# Smart_Garden.net
KiCad netlist of a schematic drawn in EAGLE
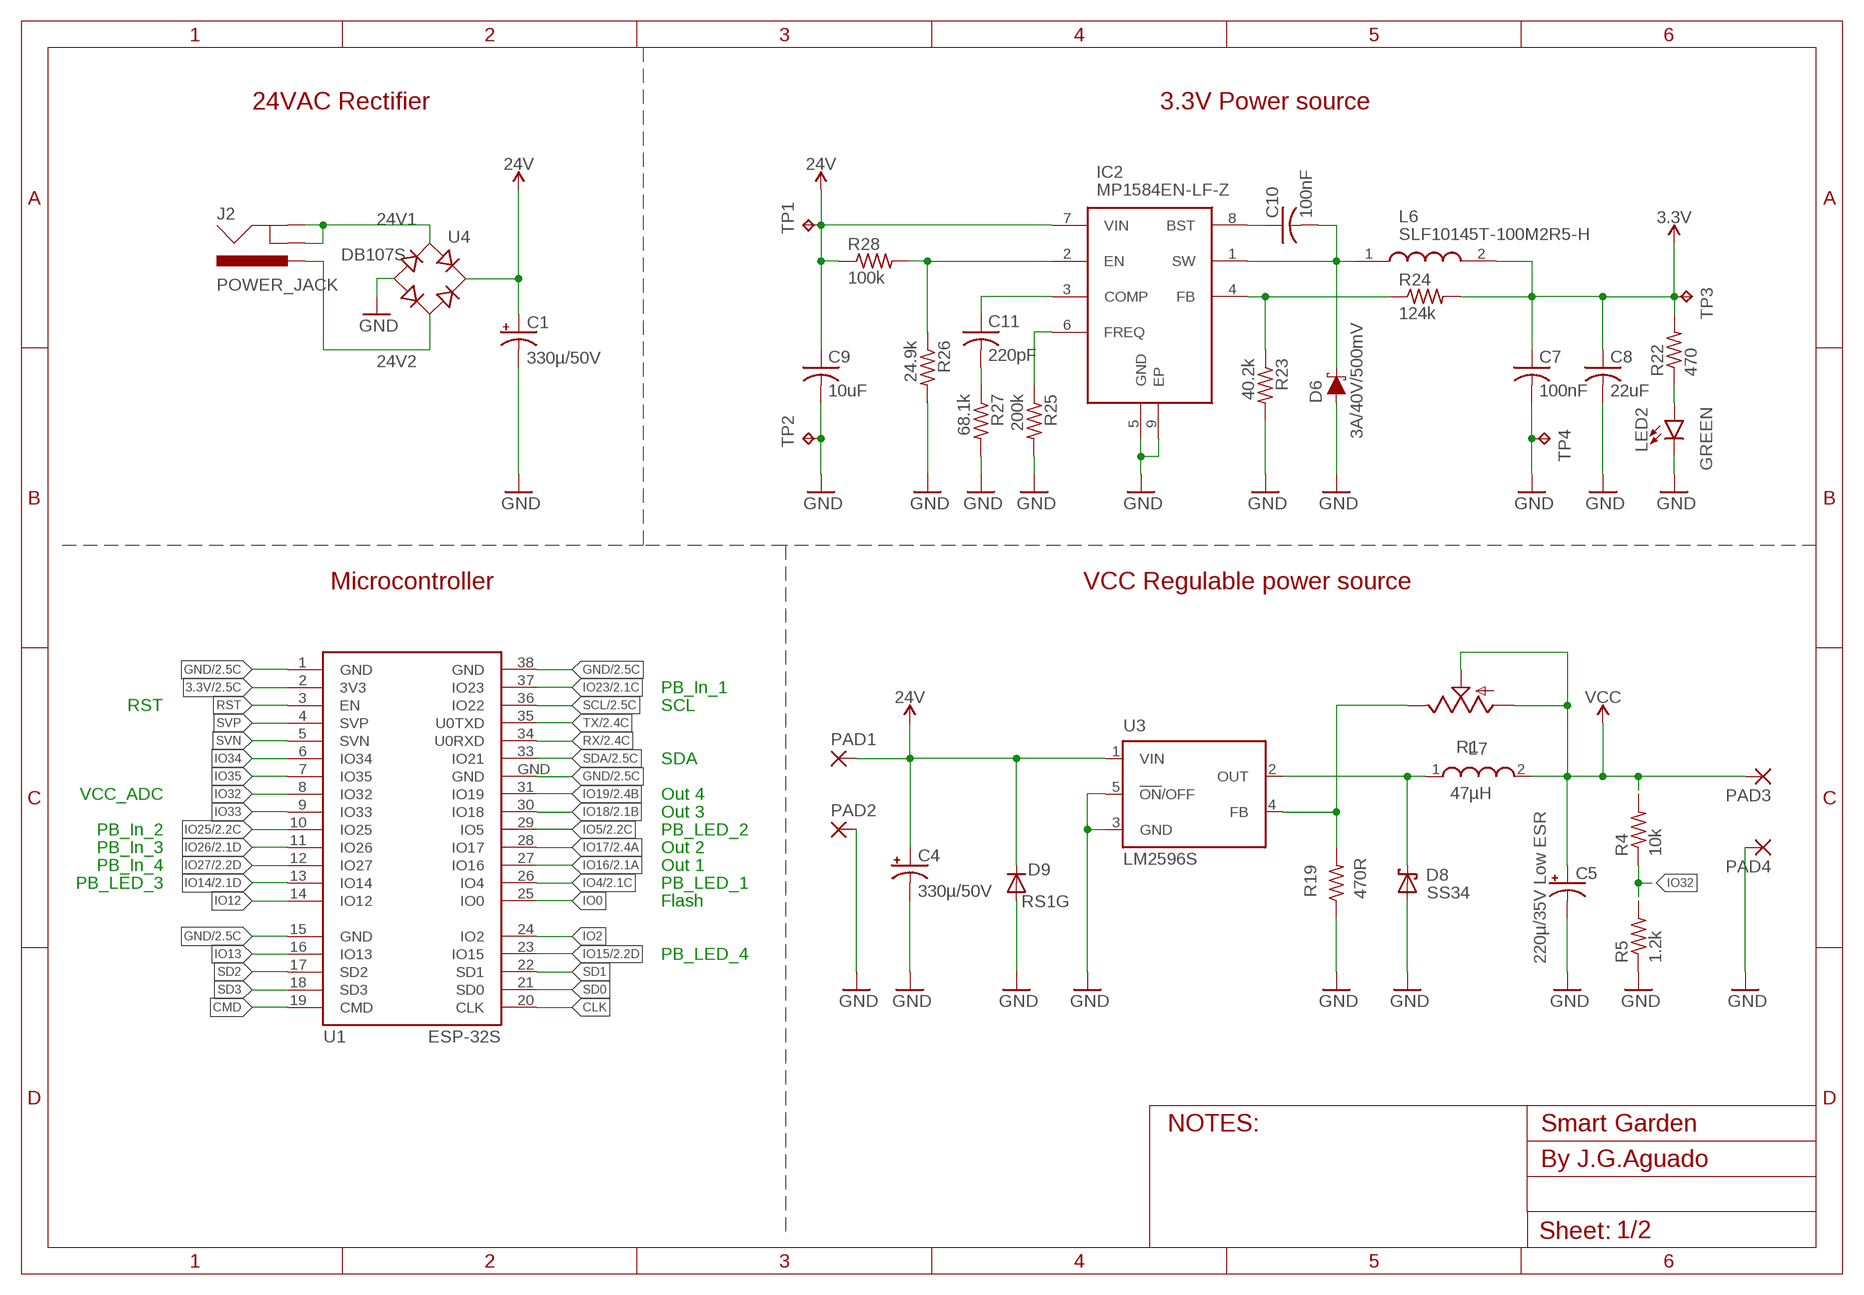
[diagram p0: schematic, sheet 1]
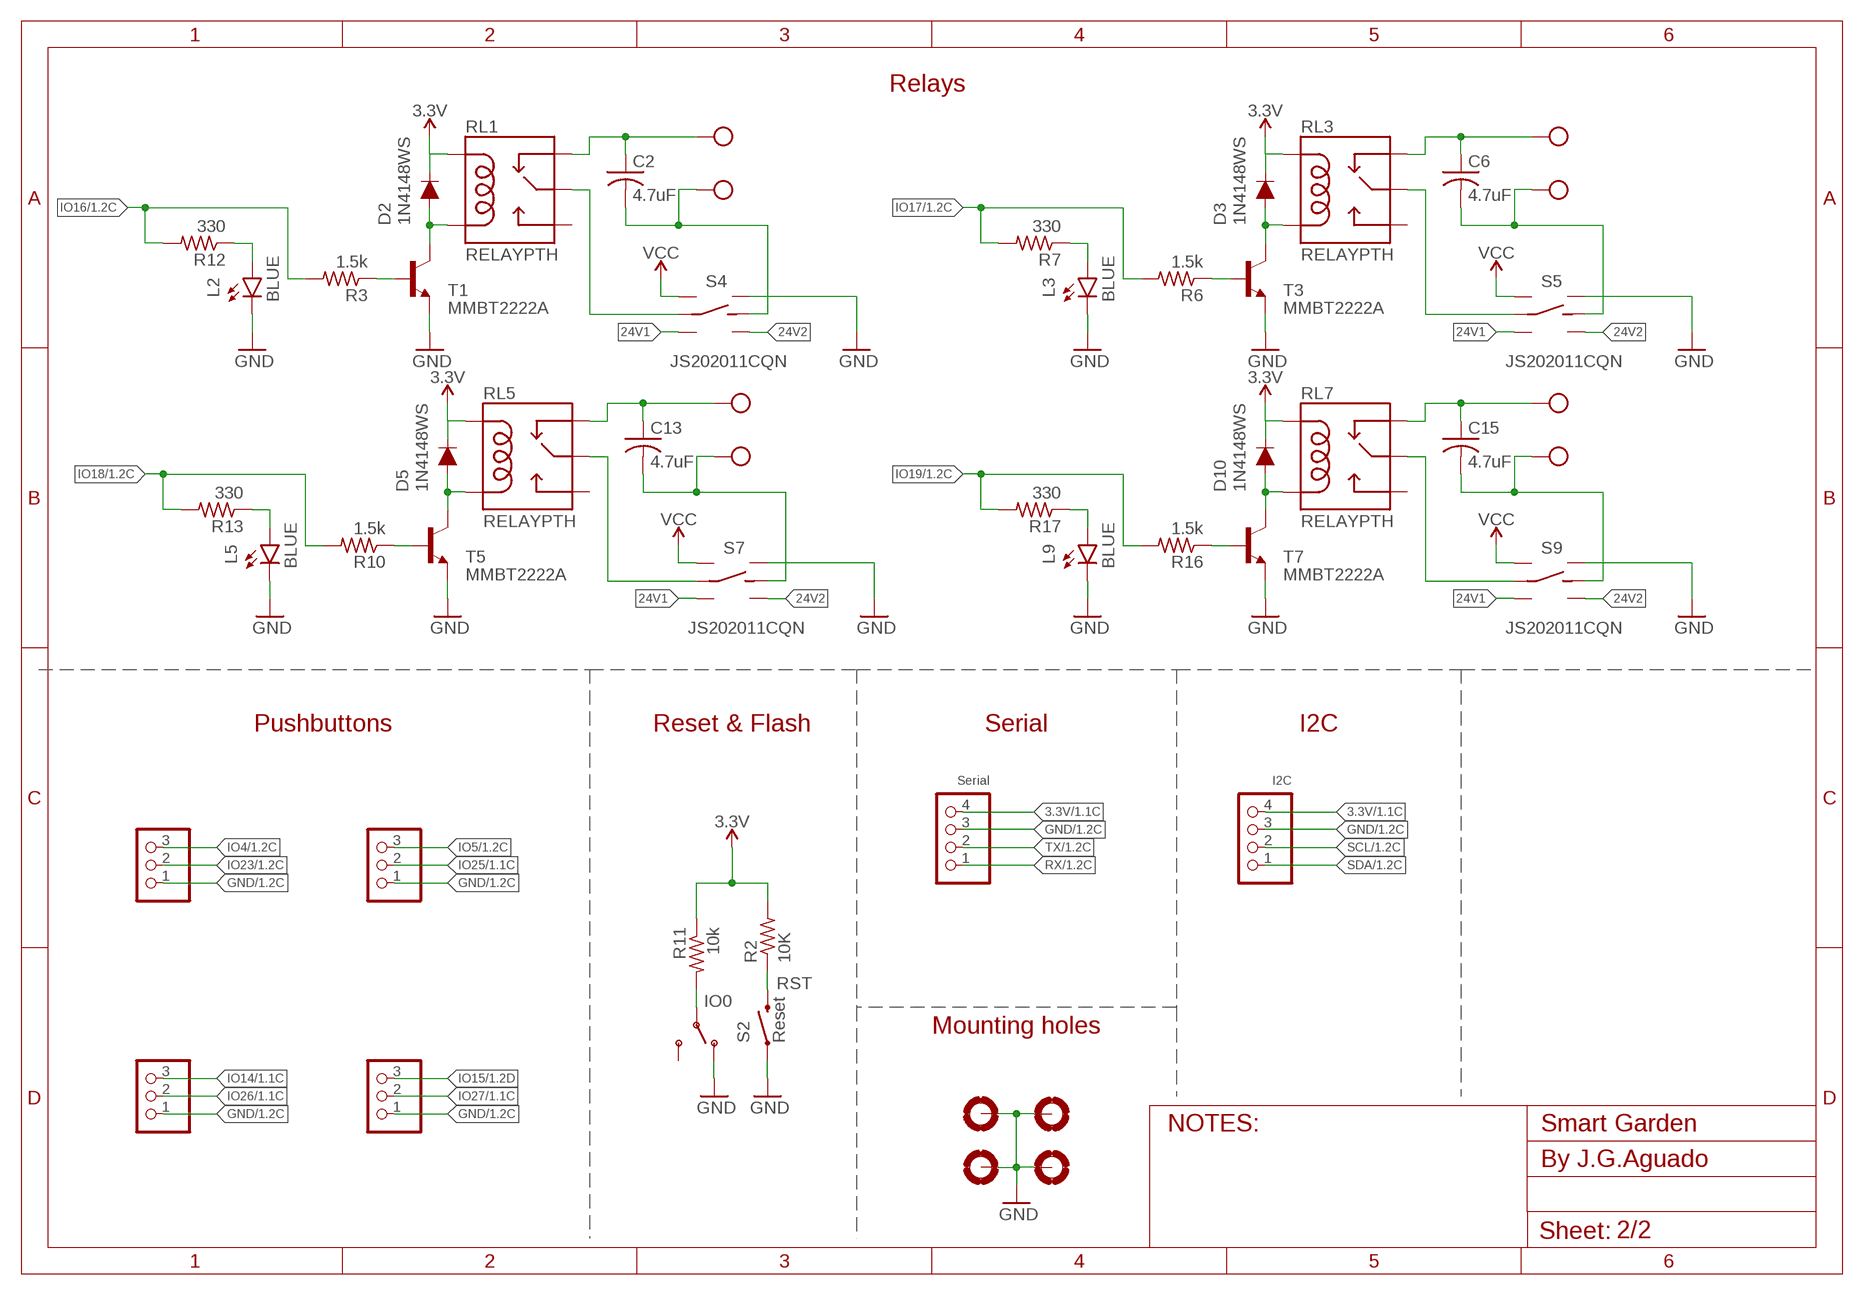
[diagram p1: schematic, sheet 2]

(export (version "E")
  (design (tool "Eeschema 10.0.6"))
  (components
    (comp (ref "C1")
      (value "330µ/50V")
      (footprint "eagle-import:PANASONIC_G")
      (fields (field (name "MF") "Panasonic"))
      (libsource (lib "eagle-import") (part "CPOL-USG"))
    )
    (comp (ref "C4")
      (value "330µ/50V")
      (footprint "eagle-import:PANASONIC_G")
      (fields (field (name "MF") "Panasonic"))
      (libsource (lib "eagle-import") (part "CPOL-USG"))
    )
    (comp (ref "C5")
      (value "220µ/35V Low ESR")
      (footprint "eagle-import:PANASONIC_F")
      (fields (field (name "MF") "Panasonic"))
      (libsource (lib "eagle-import") (part "CPOL-USF"))
    )
    (comp (ref "C7")
      (value "100nF")
      (footprint "eagle-import:C0603")
      (libsource (lib "eagle-import") (part "C-USC0603"))
    )
    (comp (ref "C8")
      (value "22uF")
      (footprint "eagle-import:C0603")
      (libsource (lib "eagle-import") (part "C-USC0603"))
    )
    (comp (ref "C9")
      (value "10uF")
      (footprint "eagle-import:C0603")
      (libsource (lib "eagle-import") (part "C-USC0603"))
    )
    (comp (ref "C10")
      (value "100nF")
      (footprint "eagle-import:C0603")
      (libsource (lib "eagle-import") (part "C-USC0603"))
    )
    (comp (ref "C11")
      (value "220pF")
      (footprint "eagle-import:C0603")
      (libsource (lib "eagle-import") (part "C-USC0603"))
    )
    (comp (ref "D6")
      (value "3A/40V/500mV")
      (footprint "eagle-import:SMA-DIODE")
      (libsource (lib "eagle-import") (part "DIODE-SCHOTTKY-B340A"))
    )
    (comp (ref "D8")
      (value "SS34")
      (footprint "eagle-import:SMB")
      (libsource (lib "eagle-import") (part "SCHOTTKY-DIODESMD"))
    )
    (comp (ref "D9")
      (value "RS1G")
      (footprint "eagle-import:DO214AC")
      (fields (field (name "MF") "multicomp"))
      (libsource (lib "eagle-import") (part "DIODE-DO214AC"))
    )
    (comp (ref "IC2")
      (value "MP1584EN-LF-Z")
      (footprint "eagle-import:SOIC127P600X170-9N")
      (fields (field (name "MOUSER_PART_NUMBER") "946-MP1584ENLFZ"))
      (libsource (lib "eagle-import") (part "MP1584EN-LF-Z"))
    )
    (comp (ref "J2")
      (value "POWER_JACK")
      (footprint "eagle-import:POWER_JACK_PTH")
      (libsource (lib "eagle-import") (part "POWER_JACK"))
    )
    (comp (ref "L6")
      (value "SLF10145T-100M2R5-H")
      (footprint "eagle-import:SLF10145")
      (fields (field (name "MOUSER_PART_NUMBER") "810-SLF10145T100M2R5"))
      (libsource (lib "eagle-import") (part "SLF10145T-100M2R5-H"))
    )
    (comp (ref "L7")
      (value "47µH")
      (footprint "eagle-import:WE-PD_1260_1245_1280_1210")
      (fields (field (name "MF") "Wuerth"))
      (libsource (lib "eagle-import") (part "WE-PD_1260/1245/1280/1210"))
    )
    (comp (ref "LED2")
      (value "GREEN")
      (footprint "eagle-import:LED-0603")
      (libsource (lib "eagle-import") (part "LED-GREEN0603"))
    )
    (comp (ref "PAD1")
      (value "2,54/1,1")
      (footprint "eagle-import:2,54_1,1")
      (libsource (lib "eagle-import") (part "2,54/1,1"))
    )
    (comp (ref "PAD2")
      (value "2,54/1,1")
      (footprint "eagle-import:2,54_1,1")
      (libsource (lib "eagle-import") (part "2,54/1,1"))
    )
    (comp (ref "PAD3")
      (value "2,54/1,1")
      (footprint "eagle-import:2,54_1,1")
      (libsource (lib "eagle-import") (part "2,54/1,1"))
    )
    (comp (ref "PAD4")
      (value "2,54/1,1")
      (footprint "eagle-import:2,54_1,1")
      (libsource (lib "eagle-import") (part "2,54/1,1"))
    )
    (comp (ref "R1")
      (value "TRIM_US-RJ9W")
      (footprint "eagle-import:RJ9W")
      (libsource (lib "eagle-import") (part "TRIM_US-RJ9W"))
    )
    (comp (ref "R4")
      (value "10k")
      (footprint "eagle-import:R0603")
      (libsource (lib "eagle-import") (part "R-US_R0603"))
    )
    (comp (ref "R5")
      (value "1.2k")
      (footprint "eagle-import:R0603")
      (libsource (lib "eagle-import") (part "R-US_R0603"))
    )
    (comp (ref "R19")
      (value "470R")
      (footprint "eagle-import:R1206")
      (libsource (lib "eagle-import") (part "R-US_R1206"))
    )
    (comp (ref "R22")
      (value "470")
      (footprint "eagle-import:R0603")
      (libsource (lib "eagle-import") (part "R-US_R0603"))
    )
    (comp (ref "R23")
      (value "40.2k")
      (footprint "eagle-import:R0603")
      (libsource (lib "eagle-import") (part "R-US_R0603"))
    )
    (comp (ref "R24")
      (value "124k")
      (footprint "eagle-import:R0603")
      (libsource (lib "eagle-import") (part "R-US_R0603"))
    )
    (comp (ref "R25")
      (value "200k")
      (footprint "eagle-import:R0603")
      (libsource (lib "eagle-import") (part "R-US_R0603"))
    )
    (comp (ref "R26")
      (value "24.9k")
      (footprint "eagle-import:R0603")
      (libsource (lib "eagle-import") (part "R-US_R0603"))
    )
    (comp (ref "R27")
      (value "68.1k")
      (footprint "eagle-import:R0603")
      (libsource (lib "eagle-import") (part "R-US_R0603"))
    )
    (comp (ref "R28")
      (value "100k")
      (footprint "eagle-import:R0603")
      (libsource (lib "eagle-import") (part "R-US_R0603"))
    )
    (comp (ref "TP1")
      (value "TPTP20SQ")
      (footprint "eagle-import:TP20SQ")
      (libsource (lib "eagle-import") (part "TPTP20SQ"))
    )
    (comp (ref "TP2")
      (value "TPTP20SQ")
      (footprint "eagle-import:TP20SQ")
      (libsource (lib "eagle-import") (part "TPTP20SQ"))
    )
    (comp (ref "TP3")
      (value "TPTP20SQ")
      (footprint "eagle-import:TP20SQ")
      (libsource (lib "eagle-import") (part "TPTP20SQ"))
    )
    (comp (ref "TP4")
      (value "TPTP20SQ")
      (footprint "eagle-import:TP20SQ")
      (libsource (lib "eagle-import") (part "TPTP20SQ"))
    )
    (comp (ref "U1")
      (value "ESP-32S")
      (footprint "eagle-import:ESP-32S")
      (libsource (lib "eagle-import") (part "ESP-32S"))
    )
    (comp (ref "U3")
      (value "LM2596S")
      (footprint "eagle-import:TO263-5")
      (fields (field (name "MF") "NATIONAL SEMICONDUCTOR") (field (name "MPN") "LM2596S-ADJ/NOPB"))
      (libsource (lib "eagle-import") (part "LM2596S"))
    )
    (comp (ref "U4")
      (value "DB107S")
      (footprint "eagle-import:DBS")
      (libsource (lib "eagle-import") (part "DB?GS107"))
    )
    (comp (ref "C2")
      (value "4.7uF")
      (footprint "eagle-import:C1206")
      (libsource (lib "eagle-import") (part "C-USC1206"))
    )
    (comp (ref "C6")
      (value "4.7uF")
      (footprint "eagle-import:C1206")
      (libsource (lib "eagle-import") (part "C-USC1206"))
    )
    (comp (ref "C13")
      (value "4.7uF")
      (footprint "eagle-import:C1206")
      (libsource (lib "eagle-import") (part "C-USC1206"))
    )
    (comp (ref "C15")
      (value "4.7uF")
      (footprint "eagle-import:C1206")
      (libsource (lib "eagle-import") (part "C-USC1206"))
    )
    (comp (ref "D2")
      (value "1N4148WS")
      (footprint "eagle-import:SOD-323")
      (libsource (lib "eagle-import") (part "DIODE-BAS16J"))
    )
    (comp (ref "D3")
      (value "1N4148WS")
      (footprint "eagle-import:SOD-323")
      (libsource (lib "eagle-import") (part "DIODE-BAS16J"))
    )
    (comp (ref "D5")
      (value "1N4148WS")
      (footprint "eagle-import:SOD-323")
      (libsource (lib "eagle-import") (part "DIODE-BAS16J"))
    )
    (comp (ref "D10")
      (value "1N4148WS")
      (footprint "eagle-import:SOD-323")
      (libsource (lib "eagle-import") (part "DIODE-BAS16J"))
    )
    (comp (ref "H1")
      (value "MOUNT-PAD-ROUND")
      (footprint "eagle-import:3,0-PAD")
      (libsource (lib "eagle-import") (part "MOUNT-PAD-ROUND"))
    )
    (comp (ref "H2")
      (value "MOUNT-PAD-ROUND")
      (footprint "eagle-import:3,0-PAD")
      (libsource (lib "eagle-import") (part "MOUNT-PAD-ROUND"))
    )
    (comp (ref "H3")
      (value "MOUNT-PAD-ROUND")
      (footprint "eagle-import:3,0-PAD")
      (libsource (lib "eagle-import") (part "MOUNT-PAD-ROUND"))
    )
    (comp (ref "H4")
      (value "MOUNT-PAD-ROUND")
      (footprint "eagle-import:3,0-PAD")
      (libsource (lib "eagle-import") (part "MOUNT-PAD-ROUND"))
    )
    (comp (ref "JP1")
      (value "Serial")
      (footprint "eagle-import:1X04")
      (libsource (lib "eagle-import") (part "PINHD-1X4"))
    )
    (comp (ref "JP2")
      (value "PINHD-1X3")
      (footprint "eagle-import:1X03")
      (libsource (lib "eagle-import") (part "PINHD-1X3"))
    )
    (comp (ref "JP3")
      (value "PINHD-1X3")
      (footprint "eagle-import:1X03")
      (libsource (lib "eagle-import") (part "PINHD-1X3"))
    )
    (comp (ref "JP4")
      (value "PINHD-1X3")
      (footprint "eagle-import:1X03")
      (libsource (lib "eagle-import") (part "PINHD-1X3"))
    )
    (comp (ref "JP5")
      (value "PINHD-1X3")
      (footprint "eagle-import:1X03")
      (libsource (lib "eagle-import") (part "PINHD-1X3"))
    )
    (comp (ref "JP6")
      (value "I2C")
      (footprint "eagle-import:1X04")
      (libsource (lib "eagle-import") (part "PINHD-1X4"))
    )
    (comp (ref "L2")
      (value "BLUE")
      (footprint "eagle-import:LED-0603")
      (libsource (lib "eagle-import") (part "LED-BLUE0603"))
    )
    (comp (ref "L3")
      (value "BLUE")
      (footprint "eagle-import:LED-0603")
      (libsource (lib "eagle-import") (part "LED-BLUE0603"))
    )
    (comp (ref "L5")
      (value "BLUE")
      (footprint "eagle-import:LED-0603")
      (libsource (lib "eagle-import") (part "LED-BLUE0603"))
    )
    (comp (ref "L9")
      (value "BLUE")
      (footprint "eagle-import:LED-0603")
      (libsource (lib "eagle-import") (part "LED-BLUE0603"))
    )
    (comp (ref "R2")
      (value "10K")
      (footprint "eagle-import:R0603")
      (libsource (lib "eagle-import") (part "R-US_R0603"))
    )
    (comp (ref "R3")
      (value "1.5k")
      (footprint "eagle-import:R0603")
      (libsource (lib "eagle-import") (part "R-US_R0603"))
    )
    (comp (ref "R6")
      (value "1.5k")
      (footprint "eagle-import:R0603")
      (libsource (lib "eagle-import") (part "R-US_R0603"))
    )
    (comp (ref "R7")
      (value "330")
      (footprint "eagle-import:R0603")
      (libsource (lib "eagle-import") (part "R-US_R0603"))
    )
    (comp (ref "R10")
      (value "1.5k")
      (footprint "eagle-import:R0603")
      (libsource (lib "eagle-import") (part "R-US_R0603"))
    )
    (comp (ref "R11")
      (value "10k")
      (footprint "eagle-import:R0603")
      (libsource (lib "eagle-import") (part "R-US_R0603"))
    )
    (comp (ref "R12")
      (value "330")
      (footprint "eagle-import:R0603")
      (libsource (lib "eagle-import") (part "R-US_R0603"))
    )
    (comp (ref "R13")
      (value "330")
      (footprint "eagle-import:R0603")
      (libsource (lib "eagle-import") (part "R-US_R0603"))
    )
    (comp (ref "R16")
      (value "1.5k")
      (footprint "eagle-import:R0603")
      (libsource (lib "eagle-import") (part "R-US_R0603"))
    )
    (comp (ref "R17")
      (value "330")
      (footprint "eagle-import:R0603")
      (libsource (lib "eagle-import") (part "R-US_R0603"))
    )
    (comp (ref "RL1")
      (value "RELAYPTH")
      (footprint "eagle-import:SRD-05VDC-SL-C")
      (libsource (lib "eagle-import") (part "RELAYPTH"))
    )
    (comp (ref "RL3")
      (value "RELAYPTH")
      (footprint "eagle-import:SRD-05VDC-SL-C")
      (libsource (lib "eagle-import") (part "RELAYPTH"))
    )
    (comp (ref "RL5")
      (value "RELAYPTH")
      (footprint "eagle-import:SRD-05VDC-SL-C")
      (libsource (lib "eagle-import") (part "RELAYPTH"))
    )
    (comp (ref "RL7")
      (value "RELAYPTH")
      (footprint "eagle-import:SRD-05VDC-SL-C")
      (libsource (lib "eagle-import") (part "RELAYPTH"))
    )
    (comp (ref "S1")
      (value "SWITCH_SPDT")
      (footprint "eagle-import:KPS-1290")
      (libsource (lib "eagle-import") (part "SWITCH_SPDT"))
    )
    (comp (ref "S2")
      (value "Reset")
      (footprint "eagle-import:TACTILE_SWITCH_TALL")
      (libsource (lib "eagle-import") (part "SWITCH-MOMENTARY-2SMD-4"))
    )
    (comp (ref "S4")
      (value "JS202011CQN")
      (footprint "eagle-import:DPDT_JS202011CQN")
      (libsource (lib "eagle-import") (part "DPDT_JS202011CQN"))
    )
    (comp (ref "S5")
      (value "JS202011CQN")
      (footprint "eagle-import:DPDT_JS202011CQN")
      (libsource (lib "eagle-import") (part "DPDT_JS202011CQN"))
    )
    (comp (ref "S7")
      (value "JS202011CQN")
      (footprint "eagle-import:DPDT_JS202011CQN")
      (libsource (lib "eagle-import") (part "DPDT_JS202011CQN"))
    )
    (comp (ref "S9")
      (value "JS202011CQN")
      (footprint "eagle-import:DPDT_JS202011CQN")
      (libsource (lib "eagle-import") (part "DPDT_JS202011CQN"))
    )
    (comp (ref "T1")
      (value "MMBT2222A")
      (footprint "eagle-import:SOT23")
      (libsource (lib "eagle-import") (part "BC847"))
    )
    (comp (ref "T3")
      (value "MMBT2222A")
      (footprint "eagle-import:SOT23")
      (libsource (lib "eagle-import") (part "BC847"))
    )
    (comp (ref "T5")
      (value "MMBT2222A")
      (footprint "eagle-import:SOT23")
      (libsource (lib "eagle-import") (part "BC847"))
    )
    (comp (ref "T7")
      (value "MMBT2222A")
      (footprint "eagle-import:SOT23")
      (libsource (lib "eagle-import") (part "BC847"))
    )
    (comp (ref "X2")
      (value "W237-102")
      (footprint "eagle-import:W237-102")
      (fields (field (name "MPN") "237-102"))
      (libsource (lib "eagle-import") (part "W237-102"))
    )
    (comp (ref "X4")
      (value "W237-102")
      (footprint "eagle-import:W237-102")
      (fields (field (name "MPN") "237-102"))
      (libsource (lib "eagle-import") (part "W237-102"))
    )
    (comp (ref "X6")
      (value "W237-102")
      (footprint "eagle-import:W237-102")
      (fields (field (name "MPN") "237-102"))
      (libsource (lib "eagle-import") (part "W237-102"))
    )
    (comp (ref "X7")
      (value "W237-102")
      (footprint "eagle-import:W237-102")
      (fields (field (name "MPN") "237-102"))
      (libsource (lib "eagle-import") (part "W237-102"))
    )
  )
  (nets
    (net (code "1") (name "3.3V") (class "Default")
      (node (ref "C7") (pin "1") (pinfunction "1_1") (pintype "passive"))
      (node (ref "C8") (pin "1") (pinfunction "1_1") (pintype "passive"))
      (node (ref "D10") (pin "C") (pinfunction "C_C") (pintype "passive"))
      (node (ref "D2") (pin "C") (pinfunction "C_C") (pintype "passive"))
      (node (ref "D3") (pin "C") (pinfunction "C_C") (pintype "passive"))
      (node (ref "D5") (pin "C") (pinfunction "C_C") (pintype "passive"))
      (node (ref "JP1") (pin "4") (pinfunction "4_4") (pintype "passive"))
      (node (ref "JP6") (pin "4") (pinfunction "4_4") (pintype "passive"))
      (node (ref "L6") (pin "2") (pinfunction "2_2") (pintype "bidirectional"))
      (node (ref "R11") (pin "1") (pinfunction "1_1") (pintype "passive"))
      (node (ref "R2") (pin "2") (pinfunction "2_2") (pintype "passive"))
      (node (ref "R22") (pin "2") (pinfunction "2_2") (pintype "passive"))
      (node (ref "R24") (pin "2") (pinfunction "2_2") (pintype "passive"))
      (node (ref "RL1") (pin "COIL1") (pinfunction "COIL1_COIL1") (pintype "bidirectional"))
      (node (ref "RL3") (pin "COIL1") (pinfunction "COIL1_COIL1") (pintype "bidirectional"))
      (node (ref "RL5") (pin "COIL1") (pinfunction "COIL1_COIL1") (pintype "bidirectional"))
      (node (ref "RL7") (pin "COIL1") (pinfunction "COIL1_COIL1") (pintype "bidirectional"))
      (node (ref "TP3") (pin "TP") (pinfunction "TP_TP") (pintype "input"))
      (node (ref "U1") (pin "2") (pinfunction "3V3_2") (pintype "power_in"))
    )
    (net (code "2") (name "24V") (class "Default")
      (node (ref "C1") (pin "+") (pinfunction "+_+") (pintype "passive"))
      (node (ref "C4") (pin "+") (pinfunction "+_+") (pintype "passive"))
      (node (ref "C9") (pin "1") (pinfunction "1_1") (pintype "passive"))
      (node (ref "D9") (pin "C") (pinfunction "C_C") (pintype "passive"))
      (node (ref "IC2") (pin "7") (pinfunction "VIN_7") (pintype "power_in"))
      (node (ref "PAD1") (pin "1") (pinfunction "P_1") (pintype "passive"))
      (node (ref "R28") (pin "1") (pinfunction "1_1") (pintype "passive"))
      (node (ref "TP1") (pin "TP") (pinfunction "TP_TP") (pintype "input"))
      (node (ref "U3") (pin "1") (pinfunction "VIN_1") (pintype "input"))
      (node (ref "U4") (pin "+") (pinfunction "+_+") (pintype "passive"))
    )
    (net (code "3") (name "24V1") (class "Default")
      (node (ref "J2") (pin "GND") (pinfunction "GND_GND") (pintype "bidirectional"))
      (node (ref "J2") (pin "GNDBREAK") (pinfunction "GNDBREAK_GNDBREAK") (pintype "bidirectional"))
      (node (ref "S4") (pin "3") (pinfunction "L2_3") (pintype "passive"))
      (node (ref "S5") (pin "3") (pinfunction "L2_3") (pintype "passive"))
      (node (ref "S7") (pin "3") (pinfunction "L2_3") (pintype "passive"))
      (node (ref "S9") (pin "3") (pinfunction "L2_3") (pintype "passive"))
      (node (ref "U4") (pin "AC1") (pinfunction "AC1_AC1") (pintype "passive"))
    )
    (net (code "4") (name "24V2") (class "Default")
      (node (ref "J2") (pin "PWR") (pinfunction "PWR_PWR") (pintype "bidirectional"))
      (node (ref "S4") (pin "6") (pinfunction "R2_6") (pintype "passive"))
      (node (ref "S5") (pin "6") (pinfunction "R2_6") (pintype "passive"))
      (node (ref "S7") (pin "6") (pinfunction "R2_6") (pintype "passive"))
      (node (ref "S9") (pin "6") (pinfunction "R2_6") (pintype "passive"))
      (node (ref "U4") (pin "AC2") (pinfunction "AC2_AC2") (pintype "passive"))
    )
    (net (code "5") (name "CLK") (class "Default")
      (node (ref "U1") (pin "20") (pinfunction "CLK_20") (pintype "bidirectional"))
    )
    (net (code "6") (name "CMD") (class "Default")
      (node (ref "U1") (pin "19") (pinfunction "CMD_19") (pintype "bidirectional"))
    )
    (net (code "7") (name "GND") (class "Default")
      (node (ref "C1") (pin "-") (pinfunction "-_-") (pintype "passive"))
      (node (ref "C4") (pin "-") (pinfunction "-_-") (pintype "passive"))
      (node (ref "C5") (pin "-") (pinfunction "-_-") (pintype "passive"))
      (node (ref "C7") (pin "2") (pinfunction "2_2") (pintype "passive"))
      (node (ref "C8") (pin "2") (pinfunction "2_2") (pintype "passive"))
      (node (ref "C9") (pin "2") (pinfunction "2_2") (pintype "passive"))
      (node (ref "D6") (pin "A") (pinfunction "A_A") (pintype "passive"))
      (node (ref "D8") (pin "A") (pinfunction "A_A") (pintype "passive"))
      (node (ref "D9") (pin "A") (pinfunction "A_A") (pintype "passive"))
      (node (ref "H1") (pin "B3,0") (pinfunction "MOUNT_B3,0") (pintype "passive"))
      (node (ref "H1") (pin "P$2") (pinfunction "MOUNT_P$2") (pintype "passive"))
      (node (ref "H1") (pin "P$3") (pinfunction "MOUNT_P$3") (pintype "passive"))
      (node (ref "H1") (pin "P$4") (pinfunction "MOUNT_P$4") (pintype "passive"))
      (node (ref "H1") (pin "P$5") (pinfunction "MOUNT_P$5") (pintype "passive"))
      (node (ref "H1") (pin "P$6") (pinfunction "MOUNT_P$6") (pintype "passive"))
      (node (ref "H1") (pin "P$7") (pinfunction "MOUNT_P$7") (pintype "passive"))
      (node (ref "H1") (pin "P$8") (pinfunction "MOUNT_P$8") (pintype "passive"))
      (node (ref "H1") (pin "P$9") (pinfunction "MOUNT_P$9") (pintype "passive"))
      (node (ref "H2") (pin "B3,0") (pinfunction "MOUNT_B3,0") (pintype "passive"))
      (node (ref "H2") (pin "P$2") (pinfunction "MOUNT_P$2") (pintype "passive"))
      (node (ref "H2") (pin "P$3") (pinfunction "MOUNT_P$3") (pintype "passive"))
      (node (ref "H2") (pin "P$4") (pinfunction "MOUNT_P$4") (pintype "passive"))
      (node (ref "H2") (pin "P$5") (pinfunction "MOUNT_P$5") (pintype "passive"))
      (node (ref "H2") (pin "P$6") (pinfunction "MOUNT_P$6") (pintype "passive"))
      (node (ref "H2") (pin "P$7") (pinfunction "MOUNT_P$7") (pintype "passive"))
      (node (ref "H2") (pin "P$8") (pinfunction "MOUNT_P$8") (pintype "passive"))
      (node (ref "H2") (pin "P$9") (pinfunction "MOUNT_P$9") (pintype "passive"))
      (node (ref "H3") (pin "B3,0") (pinfunction "MOUNT_B3,0") (pintype "passive"))
      (node (ref "H3") (pin "P$2") (pinfunction "MOUNT_P$2") (pintype "passive"))
      (node (ref "H3") (pin "P$3") (pinfunction "MOUNT_P$3") (pintype "passive"))
      (node (ref "H3") (pin "P$4") (pinfunction "MOUNT_P$4") (pintype "passive"))
      (node (ref "H3") (pin "P$5") (pinfunction "MOUNT_P$5") (pintype "passive"))
      (node (ref "H3") (pin "P$6") (pinfunction "MOUNT_P$6") (pintype "passive"))
      (node (ref "H3") (pin "P$7") (pinfunction "MOUNT_P$7") (pintype "passive"))
      (node (ref "H3") (pin "P$8") (pinfunction "MOUNT_P$8") (pintype "passive"))
      (node (ref "H3") (pin "P$9") (pinfunction "MOUNT_P$9") (pintype "passive"))
      (node (ref "H4") (pin "B3,0") (pinfunction "MOUNT_B3,0") (pintype "passive"))
      (node (ref "H4") (pin "P$2") (pinfunction "MOUNT_P$2") (pintype "passive"))
      (node (ref "H4") (pin "P$3") (pinfunction "MOUNT_P$3") (pintype "passive"))
      (node (ref "H4") (pin "P$4") (pinfunction "MOUNT_P$4") (pintype "passive"))
      (node (ref "H4") (pin "P$5") (pinfunction "MOUNT_P$5") (pintype "passive"))
      (node (ref "H4") (pin "P$6") (pinfunction "MOUNT_P$6") (pintype "passive"))
      (node (ref "H4") (pin "P$7") (pinfunction "MOUNT_P$7") (pintype "passive"))
      (node (ref "H4") (pin "P$8") (pinfunction "MOUNT_P$8") (pintype "passive"))
      (node (ref "H4") (pin "P$9") (pinfunction "MOUNT_P$9") (pintype "passive"))
      (node (ref "IC2") (pin "5") (pinfunction "GND_5") (pintype "power_in"))
      (node (ref "IC2") (pin "9") (pinfunction "EP_9") (pintype "bidirectional"))
      (node (ref "JP1") (pin "3") (pinfunction "3_3") (pintype "passive"))
      (node (ref "JP2") (pin "1") (pinfunction "1_1") (pintype "passive"))
      (node (ref "JP3") (pin "1") (pinfunction "1_1") (pintype "passive"))
      (node (ref "JP4") (pin "1") (pinfunction "1_1") (pintype "passive"))
      (node (ref "JP5") (pin "1") (pinfunction "1_1") (pintype "passive"))
      (node (ref "JP6") (pin "3") (pinfunction "3_3") (pintype "passive"))
      (node (ref "L2") (pin "C") (pinfunction "C_C") (pintype "passive"))
      (node (ref "L3") (pin "C") (pinfunction "C_C") (pintype "passive"))
      (node (ref "L5") (pin "C") (pinfunction "C_C") (pintype "passive"))
      (node (ref "L9") (pin "C") (pinfunction "C_C") (pintype "passive"))
      (node (ref "LED2") (pin "C") (pinfunction "C_C") (pintype "passive"))
      (node (ref "PAD2") (pin "1") (pinfunction "P_1") (pintype "passive"))
      (node (ref "PAD4") (pin "1") (pinfunction "P_1") (pintype "passive"))
      (node (ref "R19") (pin "1") (pinfunction "1_1") (pintype "passive"))
      (node (ref "R23") (pin "2") (pinfunction "2_2") (pintype "passive"))
      (node (ref "R25") (pin "2") (pinfunction "2_2") (pintype "passive"))
      (node (ref "R26") (pin "2") (pinfunction "2_2") (pintype "passive"))
      (node (ref "R27") (pin "2") (pinfunction "2_2") (pintype "passive"))
      (node (ref "R5") (pin "1") (pinfunction "1_1") (pintype "passive"))
      (node (ref "S1") (pin "O") (pinfunction "O_O") (pintype "passive"))
      (node (ref "S2") (pin "A2") (pinfunction "1_A2") (pintype "passive"))
      (node (ref "S4") (pin "4") (pinfunction "R1_4") (pintype "passive"))
      (node (ref "S5") (pin "4") (pinfunction "R1_4") (pintype "passive"))
      (node (ref "S7") (pin "4") (pinfunction "R1_4") (pintype "passive"))
      (node (ref "S9") (pin "4") (pinfunction "R1_4") (pintype "passive"))
      (node (ref "T1") (pin "2") (pinfunction "E_2") (pintype "passive"))
      (node (ref "T3") (pin "2") (pinfunction "E_2") (pintype "passive"))
      (node (ref "T5") (pin "2") (pinfunction "E_2") (pintype "passive"))
      (node (ref "T7") (pin "2") (pinfunction "E_2") (pintype "passive"))
      (node (ref "TP2") (pin "TP") (pinfunction "TP_TP") (pintype "input"))
      (node (ref "TP4") (pin "TP") (pinfunction "TP_TP") (pintype "input"))
      (node (ref "U1") (pin "1") (pinfunction "GND_1") (pintype "power_in"))
      (node (ref "U1") (pin "15") (pinfunction "GND_15") (pintype "power_in"))
      (node (ref "U1") (pin "38") (pinfunction "GND_38") (pintype "power_in"))
      (node (ref "U1") (pin "GND") (pinfunction "GND_GND") (pintype "power_in"))
      (node (ref "U3") (pin "3") (pinfunction "GND_3") (pintype "power_in"))
      (node (ref "U3") (pin "5") (pinfunction "~{ON}/OFF_5") (pintype "input"))
      (node (ref "U4") (pin "-") (pinfunction "-_-") (pintype "passive"))
    )
    (net (code "8") (name "IO0") (class "Default")
      (node (ref "R11") (pin "2") (pinfunction "2_2") (pintype "passive"))
      (node (ref "S1") (pin "P") (pinfunction "P_P") (pintype "passive"))
      (node (ref "U1") (pin "25") (pinfunction "IO0_25") (pintype "bidirectional"))
    )
    (net (code "9") (name "IO2") (class "Default")
      (node (ref "U1") (pin "24") (pinfunction "IO2_24") (pintype "bidirectional"))
    )
    (net (code "10") (name "IO4") (class "Default")
      (node (ref "JP5") (pin "3") (pinfunction "3_3") (pintype "passive"))
      (node (ref "U1") (pin "26") (pinfunction "IO4_26") (pintype "bidirectional"))
    )
    (net (code "11") (name "IO5") (class "Default")
      (node (ref "JP4") (pin "3") (pinfunction "3_3") (pintype "passive"))
      (node (ref "U1") (pin "29") (pinfunction "IO5_29") (pintype "bidirectional"))
    )
    (net (code "12") (name "IO12") (class "Default")
      (node (ref "U1") (pin "14") (pinfunction "IO12_14") (pintype "bidirectional"))
    )
    (net (code "13") (name "IO13") (class "Default")
      (node (ref "U1") (pin "16") (pinfunction "IO13_16") (pintype "bidirectional"))
    )
    (net (code "14") (name "IO14") (class "Default")
      (node (ref "JP3") (pin "3") (pinfunction "3_3") (pintype "passive"))
      (node (ref "U1") (pin "13") (pinfunction "IO14_13") (pintype "bidirectional"))
    )
    (net (code "15") (name "IO15") (class "Default")
      (node (ref "JP2") (pin "3") (pinfunction "3_3") (pintype "passive"))
      (node (ref "U1") (pin "23") (pinfunction "IO15_23") (pintype "bidirectional"))
    )
    (net (code "16") (name "IO16") (class "Default")
      (node (ref "R12") (pin "2") (pinfunction "2_2") (pintype "passive"))
      (node (ref "R3") (pin "2") (pinfunction "2_2") (pintype "passive"))
      (node (ref "U1") (pin "27") (pinfunction "IO16_27") (pintype "bidirectional"))
    )
    (net (code "17") (name "IO17") (class "Default")
      (node (ref "R6") (pin "2") (pinfunction "2_2") (pintype "passive"))
      (node (ref "R7") (pin "2") (pinfunction "2_2") (pintype "passive"))
      (node (ref "U1") (pin "28") (pinfunction "IO17_28") (pintype "bidirectional"))
    )
    (net (code "18") (name "IO18") (class "Default")
      (node (ref "R10") (pin "2") (pinfunction "2_2") (pintype "passive"))
      (node (ref "R13") (pin "2") (pinfunction "2_2") (pintype "passive"))
      (node (ref "U1") (pin "30") (pinfunction "IO18_30") (pintype "bidirectional"))
    )
    (net (code "19") (name "IO19") (class "Default")
      (node (ref "R16") (pin "2") (pinfunction "2_2") (pintype "passive"))
      (node (ref "R17") (pin "2") (pinfunction "2_2") (pintype "passive"))
      (node (ref "U1") (pin "31") (pinfunction "IO19_31") (pintype "bidirectional"))
    )
    (net (code "20") (name "IO23") (class "Default")
      (node (ref "JP5") (pin "2") (pinfunction "2_2") (pintype "passive"))
      (node (ref "U1") (pin "37") (pinfunction "IO23_37") (pintype "bidirectional"))
    )
    (net (code "21") (name "IO25") (class "Default")
      (node (ref "JP4") (pin "2") (pinfunction "2_2") (pintype "passive"))
      (node (ref "U1") (pin "10") (pinfunction "IO25_10") (pintype "bidirectional"))
    )
    (net (code "22") (name "IO26") (class "Default")
      (node (ref "JP3") (pin "2") (pinfunction "2_2") (pintype "passive"))
      (node (ref "U1") (pin "11") (pinfunction "IO26_11") (pintype "bidirectional"))
    )
    (net (code "23") (name "IO27") (class "Default")
      (node (ref "JP2") (pin "2") (pinfunction "2_2") (pintype "passive"))
      (node (ref "U1") (pin "12") (pinfunction "IO27_12") (pintype "bidirectional"))
    )
    (net (code "24") (name "IO32") (class "Default")
      (node (ref "R4") (pin "1") (pinfunction "1_1") (pintype "passive"))
      (node (ref "R5") (pin "2") (pinfunction "2_2") (pintype "passive"))
      (node (ref "U1") (pin "8") (pinfunction "IO32_8") (pintype "bidirectional"))
    )
    (net (code "25") (name "IO33") (class "Default")
      (node (ref "U1") (pin "9") (pinfunction "IO33_9") (pintype "bidirectional"))
    )
    (net (code "26") (name "IO34") (class "Default")
      (node (ref "U1") (pin "6") (pinfunction "IO34_6") (pintype "bidirectional"))
    )
    (net (code "27") (name "IO35") (class "Default")
      (node (ref "U1") (pin "7") (pinfunction "IO35_7") (pintype "bidirectional"))
    )
    (net (code "28") (name "Net-(C11-Pad2)") (class "Default")
      (node (ref "C11") (pin "2") (pinfunction "2_2") (pintype "passive"))
      (node (ref "R27") (pin "1") (pinfunction "1_1") (pintype "passive"))
    )
    (net (code "29") (name "Net-(IC2-BST)") (class "Default")
      (node (ref "C10") (pin "1") (pinfunction "1_1") (pintype "passive"))
      (node (ref "IC2") (pin "8") (pinfunction "BST_8") (pintype "input"))
    )
    (net (code "30") (name "Net-(IC2-COMP)") (class "Default")
      (node (ref "C11") (pin "1") (pinfunction "1_1") (pintype "passive"))
      (node (ref "IC2") (pin "3") (pinfunction "COMP_3") (pintype "bidirectional"))
    )
    (net (code "31") (name "Net-(IC2-EN)") (class "Default")
      (node (ref "IC2") (pin "2") (pinfunction "EN_2") (pintype "input"))
      (node (ref "R26") (pin "1") (pinfunction "1_1") (pintype "passive"))
      (node (ref "R28") (pin "2") (pinfunction "2_2") (pintype "passive"))
    )
    (net (code "32") (name "Net-(IC2-FB)") (class "Default")
      (node (ref "IC2") (pin "4") (pinfunction "FB_4") (pintype "input"))
      (node (ref "R23") (pin "1") (pinfunction "1_1") (pintype "passive"))
      (node (ref "R24") (pin "1") (pinfunction "1_1") (pintype "passive"))
    )
    (net (code "33") (name "Net-(IC2-FREQ)") (class "Default")
      (node (ref "IC2") (pin "6") (pinfunction "FREQ_6") (pintype "input"))
      (node (ref "R25") (pin "1") (pinfunction "1_1") (pintype "passive"))
    )
    (net (code "34") (name "Net-(IC2-SW)") (class "Default")
      (node (ref "C10") (pin "2") (pinfunction "2_2") (pintype "passive"))
      (node (ref "D6") (pin "C") (pinfunction "C_C") (pintype "passive"))
      (node (ref "IC2") (pin "1") (pinfunction "SW_1") (pintype "output"))
      (node (ref "L6") (pin "1") (pinfunction "1_1") (pintype "bidirectional"))
    )
    (net (code "35") (name "Net-(L2-PadA)") (class "Default")
      (node (ref "L2") (pin "A") (pinfunction "A_A") (pintype "passive"))
      (node (ref "R12") (pin "1") (pinfunction "1_1") (pintype "passive"))
    )
    (net (code "36") (name "Net-(L3-PadA)") (class "Default")
      (node (ref "L3") (pin "A") (pinfunction "A_A") (pintype "passive"))
      (node (ref "R7") (pin "1") (pinfunction "1_1") (pintype "passive"))
    )
    (net (code "37") (name "Net-(L5-PadA)") (class "Default")
      (node (ref "L5") (pin "A") (pinfunction "A_A") (pintype "passive"))
      (node (ref "R13") (pin "1") (pinfunction "1_1") (pintype "passive"))
    )
    (net (code "38") (name "Net-(L9-PadA)") (class "Default")
      (node (ref "L9") (pin "A") (pinfunction "A_A") (pintype "passive"))
      (node (ref "R17") (pin "1") (pinfunction "1_1") (pintype "passive"))
    )
    (net (code "39") (name "Net-(LED2-PadA)") (class "Default")
      (node (ref "LED2") (pin "A") (pinfunction "A_A") (pintype "passive"))
      (node (ref "R22") (pin "1") (pinfunction "1_1") (pintype "passive"))
    )
    (net (code "40") (name "Net-(RL1-SWCLOSE)") (class "Default")
      (node (ref "C2") (pin "1") (pinfunction "1_1") (pintype "passive"))
      (node (ref "RL1") (pin "SWCLOSED") (pinfunction "SWCLOSE_SWCLOSED") (pintype "bidirectional"))
      (node (ref "X7") (pin "1") (pinfunction "KL_1") (pintype "passive"))
    )
    (net (code "41") (name "Net-(RL3-SWCLOSE)") (class "Default")
      (node (ref "C6") (pin "1") (pinfunction "1_1") (pintype "passive"))
      (node (ref "RL3") (pin "SWCLOSED") (pinfunction "SWCLOSE_SWCLOSED") (pintype "bidirectional"))
      (node (ref "X2") (pin "1") (pinfunction "KL_1") (pintype "passive"))
    )
    (net (code "42") (name "Net-(RL5-SWCLOSE)") (class "Default")
      (node (ref "C13") (pin "1") (pinfunction "1_1") (pintype "passive"))
      (node (ref "RL5") (pin "SWCLOSED") (pinfunction "SWCLOSE_SWCLOSED") (pintype "bidirectional"))
      (node (ref "X4") (pin "1") (pinfunction "KL_1") (pintype "passive"))
    )
    (net (code "43") (name "Net-(RL7-SWCLOSE)") (class "Default")
      (node (ref "C15") (pin "1") (pinfunction "1_1") (pintype "passive"))
      (node (ref "RL7") (pin "SWCLOSED") (pinfunction "SWCLOSE_SWCLOSED") (pintype "bidirectional"))
      (node (ref "X6") (pin "1") (pinfunction "KL_1") (pintype "passive"))
    )
    (net (code "44") (name "Net-(S4-LC)") (class "Default")
      (node (ref "RL1") (pin "SWCOMMON") (pinfunction "SWCOMMON_SWCOMMON") (pintype "bidirectional"))
      (node (ref "S4") (pin "2") (pinfunction "LC_2") (pintype "passive"))
    )
    (net (code "45") (name "Net-(S4-RC)") (class "Default")
      (node (ref "C2") (pin "2") (pinfunction "2_2") (pintype "passive"))
      (node (ref "S4") (pin "5") (pinfunction "RC_5") (pintype "passive"))
      (node (ref "X7") (pin "2") (pinfunction "KL_2") (pintype "passive"))
    )
    (net (code "46") (name "Net-(S5-LC)") (class "Default")
      (node (ref "RL3") (pin "SWCOMMON") (pinfunction "SWCOMMON_SWCOMMON") (pintype "bidirectional"))
      (node (ref "S5") (pin "2") (pinfunction "LC_2") (pintype "passive"))
    )
    (net (code "47") (name "Net-(S5-RC)") (class "Default")
      (node (ref "C6") (pin "2") (pinfunction "2_2") (pintype "passive"))
      (node (ref "S5") (pin "5") (pinfunction "RC_5") (pintype "passive"))
      (node (ref "X2") (pin "2") (pinfunction "KL_2") (pintype "passive"))
    )
    (net (code "48") (name "Net-(S7-LC)") (class "Default")
      (node (ref "RL5") (pin "SWCOMMON") (pinfunction "SWCOMMON_SWCOMMON") (pintype "bidirectional"))
      (node (ref "S7") (pin "2") (pinfunction "LC_2") (pintype "passive"))
    )
    (net (code "49") (name "Net-(S7-RC)") (class "Default")
      (node (ref "C13") (pin "2") (pinfunction "2_2") (pintype "passive"))
      (node (ref "S7") (pin "5") (pinfunction "RC_5") (pintype "passive"))
      (node (ref "X4") (pin "2") (pinfunction "KL_2") (pintype "passive"))
    )
    (net (code "50") (name "Net-(S9-LC)") (class "Default")
      (node (ref "RL7") (pin "SWCOMMON") (pinfunction "SWCOMMON_SWCOMMON") (pintype "bidirectional"))
      (node (ref "S9") (pin "2") (pinfunction "LC_2") (pintype "passive"))
    )
    (net (code "51") (name "Net-(S9-RC)") (class "Default")
      (node (ref "C15") (pin "2") (pinfunction "2_2") (pintype "passive"))
      (node (ref "S9") (pin "5") (pinfunction "RC_5") (pintype "passive"))
      (node (ref "X6") (pin "2") (pinfunction "KL_2") (pintype "passive"))
    )
    (net (code "52") (name "Net-(T1-B)") (class "Default")
      (node (ref "R3") (pin "1") (pinfunction "1_1") (pintype "passive"))
      (node (ref "T1") (pin "1") (pinfunction "B_1") (pintype "passive"))
    )
    (net (code "53") (name "Net-(T1-C)") (class "Default")
      (node (ref "D2") (pin "A") (pinfunction "A_A") (pintype "passive"))
      (node (ref "RL1") (pin "COIL0") (pinfunction "COIL0_COIL0") (pintype "bidirectional"))
      (node (ref "T1") (pin "3") (pinfunction "C_3") (pintype "passive"))
    )
    (net (code "54") (name "Net-(T3-B)") (class "Default")
      (node (ref "R6") (pin "1") (pinfunction "1_1") (pintype "passive"))
      (node (ref "T3") (pin "1") (pinfunction "B_1") (pintype "passive"))
    )
    (net (code "55") (name "Net-(T3-C)") (class "Default")
      (node (ref "D3") (pin "A") (pinfunction "A_A") (pintype "passive"))
      (node (ref "RL3") (pin "COIL0") (pinfunction "COIL0_COIL0") (pintype "bidirectional"))
      (node (ref "T3") (pin "3") (pinfunction "C_3") (pintype "passive"))
    )
    (net (code "56") (name "Net-(T5-B)") (class "Default")
      (node (ref "R10") (pin "1") (pinfunction "1_1") (pintype "passive"))
      (node (ref "T5") (pin "1") (pinfunction "B_1") (pintype "passive"))
    )
    (net (code "57") (name "Net-(T5-C)") (class "Default")
      (node (ref "D5") (pin "A") (pinfunction "A_A") (pintype "passive"))
      (node (ref "RL5") (pin "COIL0") (pinfunction "COIL0_COIL0") (pintype "bidirectional"))
      (node (ref "T5") (pin "3") (pinfunction "C_3") (pintype "passive"))
    )
    (net (code "58") (name "Net-(T7-B)") (class "Default")
      (node (ref "R16") (pin "1") (pinfunction "1_1") (pintype "passive"))
      (node (ref "T7") (pin "1") (pinfunction "B_1") (pintype "passive"))
    )
    (net (code "59") (name "Net-(T7-C)") (class "Default")
      (node (ref "D10") (pin "A") (pinfunction "A_A") (pintype "passive"))
      (node (ref "RL7") (pin "COIL0") (pinfunction "COIL0_COIL0") (pintype "bidirectional"))
      (node (ref "T7") (pin "3") (pinfunction "C_3") (pintype "passive"))
    )
    (net (code "60") (name "Net-(U3-FB)") (class "Default")
      (node (ref "R1") (pin "E") (pinfunction "E_E") (pintype "passive"))
      (node (ref "R19") (pin "2") (pinfunction "2_2") (pintype "passive"))
      (node (ref "U3") (pin "4") (pinfunction "FB_4") (pintype "input"))
    )
    (net (code "61") (name "Net-(U3-OUT)") (class "Default")
      (node (ref "D8") (pin "C") (pinfunction "C_C") (pintype "passive"))
      (node (ref "L7") (pin "1") (pinfunction "1_1") (pintype "passive"))
      (node (ref "U3") (pin "2") (pinfunction "OUT_2") (pintype "output"))
    )
    (net (code "62") (name "RST") (class "Default")
      (node (ref "R2") (pin "1") (pinfunction "1_1") (pintype "passive"))
      (node (ref "S2") (pin "B2") (pinfunction "2_B2") (pintype "passive"))
      (node (ref "U1") (pin "3") (pinfunction "EN_3") (pintype "input"))
    )
    (net (code "63") (name "RX") (class "Default")
      (node (ref "JP1") (pin "1") (pinfunction "1_1") (pintype "passive"))
      (node (ref "U1") (pin "34") (pinfunction "U0RXD_34") (pintype "bidirectional"))
    )
    (net (code "64") (name "SCL") (class "Default")
      (node (ref "JP6") (pin "2") (pinfunction "2_2") (pintype "passive"))
      (node (ref "U1") (pin "36") (pinfunction "IO22_36") (pintype "bidirectional"))
    )
    (net (code "65") (name "SD0") (class "Default")
      (node (ref "U1") (pin "21") (pinfunction "SD0_21") (pintype "bidirectional"))
    )
    (net (code "66") (name "SD1") (class "Default")
      (node (ref "U1") (pin "22") (pinfunction "SD1_22") (pintype "bidirectional"))
    )
    (net (code "67") (name "SD2") (class "Default")
      (node (ref "U1") (pin "17") (pinfunction "SD2_17") (pintype "bidirectional"))
    )
    (net (code "68") (name "SD3") (class "Default")
      (node (ref "U1") (pin "18") (pinfunction "SD3_18") (pintype "bidirectional"))
    )
    (net (code "69") (name "SDA") (class "Default")
      (node (ref "JP6") (pin "1") (pinfunction "1_1") (pintype "passive"))
      (node (ref "U1") (pin "33") (pinfunction "IO21_33") (pintype "bidirectional"))
    )
    (net (code "70") (name "SVN") (class "Default")
      (node (ref "U1") (pin "5") (pinfunction "SVN_5") (pintype "bidirectional"))
    )
    (net (code "71") (name "SVP") (class "Default")
      (node (ref "U1") (pin "4") (pinfunction "SVP_4") (pintype "bidirectional"))
    )
    (net (code "72") (name "TX") (class "Default")
      (node (ref "JP1") (pin "2") (pinfunction "2_2") (pintype "passive"))
      (node (ref "U1") (pin "35") (pinfunction "U0TXD_35") (pintype "bidirectional"))
    )
    (net (code "73") (name "VCC") (class "Default")
      (node (ref "C5") (pin "+") (pinfunction "+_+") (pintype "passive"))
      (node (ref "L7") (pin "2") (pinfunction "2_2") (pintype "passive"))
      (node (ref "PAD3") (pin "1") (pinfunction "P_1") (pintype "passive"))
      (node (ref "R1") (pin "A") (pinfunction "A_A") (pintype "passive"))
      (node (ref "R1") (pin "S") (pinfunction "S_S") (pintype "passive"))
      (node (ref "R4") (pin "2") (pinfunction "2_2") (pintype "passive"))
      (node (ref "S4") (pin "1") (pinfunction "L1_1") (pintype "passive"))
      (node (ref "S5") (pin "1") (pinfunction "L1_1") (pintype "passive"))
      (node (ref "S7") (pin "1") (pinfunction "L1_1") (pintype "passive"))
      (node (ref "S9") (pin "1") (pinfunction "L1_1") (pintype "passive"))
    )
    (net (code "74") (name "unconnected-(RL1-PadSWOPEN)") (class "Default")
      (node (ref "RL1") (pin "SWOPEN") (pinfunction "SWOPEN_SWOPEN") (pintype "bidirectional"))
    )
    (net (code "75") (name "unconnected-(RL3-PadSWOPEN)") (class "Default")
      (node (ref "RL3") (pin "SWOPEN") (pinfunction "SWOPEN_SWOPEN") (pintype "bidirectional"))
    )
    (net (code "76") (name "unconnected-(RL5-PadSWOPEN)") (class "Default")
      (node (ref "RL5") (pin "SWOPEN") (pinfunction "SWOPEN_SWOPEN") (pintype "bidirectional"))
    )
    (net (code "77") (name "unconnected-(RL7-PadSWOPEN)") (class "Default")
      (node (ref "RL7") (pin "SWOPEN") (pinfunction "SWOPEN_SWOPEN") (pintype "bidirectional"))
    )
    (net (code "78") (name "unconnected-(S1-PadS)") (class "Default")
      (node (ref "S1") (pin "S") (pinfunction "S_S") (pintype "passive"))
    )
  )
)
